# 09_ConsumptionBoard.net
KiCad netlist of a schematic drawn in Altium Designer
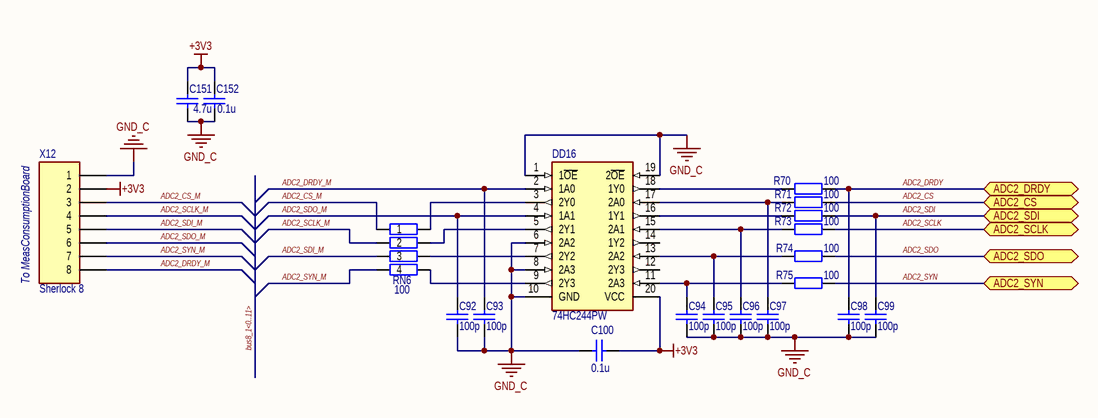
[diagram p0: 09_ConsumptionBoard.SchDoc]

(export (version "E")
  (design (tool "Eeschema 10.0.6"))
  (components
    (comp (ref "C92")
      (value "100p")
      (footprint "mainLib:SMD_C_0603")
      (description "SMD C 0603 MURATA 100V 5% NP0")
      (fields (field (name "PARTNUMBER") "GRM1885C2A101JA01") (field (name "MANUFACTURER") "MURATA"))
      (libsource (lib "mainRCLib") (part "C0603 100p 100V 5%"))
    )
    (comp (ref "C93")
      (value "100p")
      (footprint "mainLib:SMD_C_0603")
      (description "SMD C 0603 MURATA 100V 5% NP0")
      (fields (field (name "PARTNUMBER") "GRM1885C2A101JA01") (field (name "MANUFACTURER") "MURATA"))
      (libsource (lib "mainRCLib") (part "C0603 100p 100V 5%"))
    )
    (comp (ref "C94")
      (value "100p")
      (footprint "mainLib:SMD_C_0603")
      (description "SMD C 0603 MURATA 100V 5% NP0")
      (fields (field (name "PARTNUMBER") "GRM1885C2A101JA01") (field (name "MANUFACTURER") "MURATA"))
      (libsource (lib "mainRCLib") (part "C0603 100p 100V 5%"))
    )
    (comp (ref "C95")
      (value "100p")
      (footprint "mainLib:SMD_C_0603")
      (description "SMD C 0603 MURATA 100V 5% NP0")
      (fields (field (name "PARTNUMBER") "GRM1885C2A101JA01") (field (name "MANUFACTURER") "MURATA"))
      (libsource (lib "mainRCLib") (part "C0603 100p 100V 5%"))
    )
    (comp (ref "C96")
      (value "100p")
      (footprint "mainLib:SMD_C_0603")
      (description "SMD C 0603 MURATA 100V 5% NP0")
      (fields (field (name "PARTNUMBER") "GRM1885C2A101JA01") (field (name "MANUFACTURER") "MURATA"))
      (libsource (lib "mainRCLib") (part "C0603 100p 100V 5%"))
    )
    (comp (ref "C97")
      (value "100p")
      (footprint "mainLib:SMD_C_0603")
      (description "SMD C 0603 MURATA 100V 5% NP0")
      (fields (field (name "PARTNUMBER") "GRM1885C2A101JA01") (field (name "MANUFACTURER") "MURATA"))
      (libsource (lib "mainRCLib") (part "C0603 100p 100V 5%"))
    )
    (comp (ref "C98")
      (value "100p")
      (footprint "mainLib:SMD_C_0603")
      (description "SMD C 0603 MURATA 100V 5% NP0")
      (fields (field (name "PARTNUMBER") "GRM1885C2A101JA01") (field (name "MANUFACTURER") "MURATA"))
      (libsource (lib "mainRCLib") (part "C0603 100p 100V 5%"))
    )
    (comp (ref "C99")
      (value "100p")
      (footprint "mainLib:SMD_C_0603")
      (description "SMD C 0603 MURATA 100V 5% NP0")
      (fields (field (name "PARTNUMBER") "GRM1885C2A101JA01") (field (name "MANUFACTURER") "MURATA"))
      (libsource (lib "mainRCLib") (part "C0603 100p 100V 5%"))
    )
    (comp (ref "C100")
      (value "0.1u")
      (footprint "mainLib:SMD_C_0603")
      (description "SMD C 0603 MURATA 50V 10% X7R")
      (fields (field (name "PARTNUMBER") "GRM188R71H104K") (field (name "MANUFACTURER") "MURATA"))
      (libsource (lib "mainRCLib") (part "C0603 0.1u 50V 10%"))
    )
    (comp (ref "C151")
      (value "4.7u")
      (footprint "mainLib:SMD_C_0805")
      (description "SMD C 0805 MURATA 50V 5% NP0")
      (fields (field (name "PARTNUMBER") "GRM21BR61E475M") (field (name "MANUFACTURER") "MURATA"))
      (libsource (lib "mainRCLib") (part "C0805 4.7u 25V 20%  X5R"))
    )
    (comp (ref "C152")
      (value "0.1u")
      (footprint "mainLib:SMD_C_0603")
      (description "SMD C 0603 MURATA 50V 10% X7R")
      (fields (field (name "PARTNUMBER") "GRM188R71H104K") (field (name "MANUFACTURER") "MURATA"))
      (libsource (lib "mainRCLib") (part "C0603 0.1u 50V 10%"))
    )
    (comp (ref "DD16")
      (value "74HC244PW")
      (footprint "mainLib:TSSOP20")
      (description "Octal Buffer/Line Driver with 3-State Outputs, PW0020A")
      (fields (field (name "MANUFACTURER") "NXP"))
      (libsource (lib "mainLib") (part "74HC244PW"))
    )
    (comp (ref "R70")
      (value "100")
      (footprint "SMD_R_0603")
      (description "SMD R 0603 VISHAY 0.1W 75V 1% 100ppm")
      (fields (field (name "PARTNUMBER") "CRCW0603100RFK") (field (name "MANUFACTURER") "VISHAY"))
      (libsource (lib "mainRCLib") (part "R0603 100 1%"))
    )
    (comp (ref "R71")
      (value "100")
      (footprint "SMD_R_0603")
      (description "SMD R 0603 VISHAY 0.1W 75V 1% 100ppm")
      (fields (field (name "PARTNUMBER") "CRCW0603100RFK") (field (name "MANUFACTURER") "VISHAY"))
      (libsource (lib "mainRCLib") (part "R0603 100 1%"))
    )
    (comp (ref "R72")
      (value "100")
      (footprint "SMD_R_0603")
      (description "SMD R 0603 VISHAY 0.1W 75V 1% 100ppm")
      (fields (field (name "PARTNUMBER") "CRCW0603100RFK") (field (name "MANUFACTURER") "VISHAY"))
      (libsource (lib "mainRCLib") (part "R0603 100 1%"))
    )
    (comp (ref "R73")
      (value "100")
      (footprint "SMD_R_0603")
      (description "SMD R 0603 VISHAY 0.1W 75V 1% 100ppm")
      (fields (field (name "PARTNUMBER") "CRCW0603100RFK") (field (name "MANUFACTURER") "VISHAY"))
      (libsource (lib "mainRCLib") (part "R0603 100 1%"))
    )
    (comp (ref "R74")
      (value "100")
      (footprint "SMD_R_0603")
      (description "SMD R 0603 VISHAY 0.1W 75V 1% 100ppm")
      (fields (field (name "PARTNUMBER") "CRCW0603100RFK") (field (name "MANUFACTURER") "VISHAY"))
      (libsource (lib "mainRCLib") (part "R0603 100 1%"))
    )
    (comp (ref "R75")
      (value "100")
      (footprint "SMD_R_0603")
      (description "SMD R 0603 VISHAY 0.1W 75V 1% 100ppm")
      (fields (field (name "PARTNUMBER") "CRCW0603100RFK") (field (name "MANUFACTURER") "VISHAY"))
      (libsource (lib "mainRCLib") (part "R0603 100 1%"))
    )
    (comp (ref "RN6")
      (value "100")
      (footprint "mainLib:CRA06S")
      (description "SMD RESISTOR ARRAY VISHAY 0.063W 50V 1% 100ppm")
      (fields (field (name "PARTNUMBER") "CRA06S083100RF") (field (name "MANUFACTURER") "VISHAY"))
      (libsource (lib "mainRCLib") (part "CRA06S 4x100 1%"))
    )
    (comp (ref "X12")
      (value "Sherlock 8")
      (footprint "mainLib:35362-0850")
      (description "Sherlock 8 Side, 2A 125V 2mm")
      (fields (field (name "PARTNUMBER") "35362-0850") (field (name "MANUFACTURER") "MOLEX"))
      (libsource (lib "mainLib") (part "35362-0850"))
    )
  )
  (nets
    (net (code "2") (name "+3V3") (class "Default")
      (node (ref "C100") (pin "2") (pinfunction "2_2") (pintype "passive"))
      (node (ref "C151") (pin "2") (pinfunction "2_2") (pintype "passive"))
      (node (ref "C152") (pin "2") (pinfunction "2_2") (pintype "passive"))
      (node (ref "DD16") (pin "20") (pinfunction "VCC_20") (pintype "power_in"))
      (node (ref "X12") (pin "2") (pinfunction "2_2") (pintype "passive"))
    )
    (net (code "3") (name "/ADC2_CS") (class "Default")
      (node (ref "R71") (pin "2") (pinfunction "2_2") (pintype "passive"))
    )
    (net (code "4") (name "/ADC2_CS_M") (class "Default")
      (node (ref "RN6") (pin "1") (pinfunction "1_1") (pintype "passive"))
      (node (ref "X12") (pin "3") (pinfunction "3_3") (pintype "passive"))
    )
    (net (code "5") (name "/ADC2_DRDY") (class "Default")
      (node (ref "C98") (pin "1") (pinfunction "1_1") (pintype "passive"))
      (node (ref "R70") (pin "2") (pinfunction "2_2") (pintype "passive"))
    )
    (net (code "6") (name "/ADC2_DRDY_M") (class "Default")
      (node (ref "C93") (pin "1") (pinfunction "1_1") (pintype "passive"))
      (node (ref "DD16") (pin "2") (pinfunction "1A0_2") (pintype "input"))
      (node (ref "X12") (pin "8") (pinfunction "8_8") (pintype "passive"))
    )
    (net (code "7") (name "/ADC2_SCLK") (class "Default")
      (node (ref "R73") (pin "2") (pinfunction "2_2") (pintype "passive"))
    )
    (net (code "8") (name "/ADC2_SCLK_M") (class "Default")
      (node (ref "RN6") (pin "2") (pinfunction "2_2") (pintype "passive"))
      (node (ref "X12") (pin "4") (pinfunction "4_4") (pintype "passive"))
    )
    (net (code "9") (name "/ADC2_SDI") (class "Default")
      (node (ref "C99") (pin "1") (pinfunction "1_1") (pintype "passive"))
      (node (ref "R72") (pin "2") (pinfunction "2_2") (pintype "passive"))
    )
    (net (code "10") (name "/ADC2_SDI_M") (class "Default")
      (node (ref "RN6") (pin "3") (pinfunction "3_3") (pintype "passive"))
      (node (ref "X12") (pin "5") (pinfunction "5_5") (pintype "passive"))
    )
    (net (code "11") (name "/ADC2_SDO") (class "Default")
      (node (ref "R74") (pin "2") (pinfunction "2_2") (pintype "passive"))
    )
    (net (code "12") (name "/ADC2_SDO_M") (class "Default")
      (node (ref "C92") (pin "1") (pinfunction "1_1") (pintype "passive"))
      (node (ref "DD16") (pin "4") (pinfunction "1A1_4") (pintype "input"))
      (node (ref "X12") (pin "6") (pinfunction "6_6") (pintype "passive"))
    )
    (net (code "13") (name "/ADC2_SYN") (class "Default")
      (node (ref "R75") (pin "2") (pinfunction "2_2") (pintype "passive"))
    )
    (net (code "14") (name "/ADC2_SYN_M") (class "Default")
      (node (ref "RN6") (pin "4") (pinfunction "4_4") (pintype "passive"))
      (node (ref "X12") (pin "7") (pinfunction "7_7") (pintype "passive"))
    )
    (net (code "16") (name "GND_C") (class "Default")
      (node (ref "C100") (pin "1") (pinfunction "1_1") (pintype "passive"))
      (node (ref "C151") (pin "1") (pinfunction "1_1") (pintype "passive"))
      (node (ref "C152") (pin "1") (pinfunction "1_1") (pintype "passive"))
      (node (ref "C92") (pin "2") (pinfunction "2_2") (pintype "passive"))
      (node (ref "C93") (pin "2") (pinfunction "2_2") (pintype "passive"))
      (node (ref "C94") (pin "2") (pinfunction "2_2") (pintype "passive"))
      (node (ref "C95") (pin "2") (pinfunction "2_2") (pintype "passive"))
      (node (ref "C96") (pin "2") (pinfunction "2_2") (pintype "passive"))
      (node (ref "C97") (pin "2") (pinfunction "2_2") (pintype "passive"))
      (node (ref "C98") (pin "2") (pinfunction "2_2") (pintype "passive"))
      (node (ref "C99") (pin "2") (pinfunction "2_2") (pintype "passive"))
      (node (ref "DD16") (pin "1") (pinfunction "1~{OE}_1") (pintype "input"))
      (node (ref "DD16") (pin "10") (pinfunction "GND_10") (pintype "power_in"))
      (node (ref "DD16") (pin "19") (pinfunction "2~{OE}_19") (pintype "input"))
      (node (ref "DD16") (pin "6") (pinfunction "2A2_6") (pintype "input"))
      (node (ref "DD16") (pin "8") (pinfunction "2A3_8") (pintype "input"))
      (node (ref "X12") (pin "1") (pinfunction "1_1") (pintype "passive"))
    )
    (net (code "17") (name "Net-(C94-Pad1)") (class "Default")
      (node (ref "C94") (pin "1") (pinfunction "1_1") (pintype "passive"))
      (node (ref "DD16") (pin "11") (pinfunction "2A3_11") (pintype "input"))
      (node (ref "R75") (pin "1") (pinfunction "1_1") (pintype "passive"))
    )
    (net (code "18") (name "Net-(C95-Pad1)") (class "Default")
      (node (ref "C95") (pin "1") (pinfunction "1_1") (pintype "passive"))
      (node (ref "DD16") (pin "13") (pinfunction "2A2_13") (pintype "input"))
      (node (ref "R74") (pin "1") (pinfunction "1_1") (pintype "passive"))
    )
    (net (code "19") (name "Net-(DD16-1Y0)") (class "Default")
      (node (ref "DD16") (pin "18") (pinfunction "1Y0_18") (pintype "output"))
      (node (ref "R70") (pin "1") (pinfunction "1_1") (pintype "passive"))
    )
    (net (code "20") (name "Net-(DD16-1Y1)") (class "Default")
      (node (ref "DD16") (pin "16") (pinfunction "1Y1_16") (pintype "output"))
      (node (ref "R72") (pin "1") (pinfunction "1_1") (pintype "passive"))
    )
    (net (code "21") (name "Net-(DD16-2A0)") (class "Default")
      (node (ref "C97") (pin "1") (pinfunction "1_1") (pintype "passive"))
      (node (ref "DD16") (pin "17") (pinfunction "2A0_17") (pintype "input"))
      (node (ref "R71") (pin "1") (pinfunction "1_1") (pintype "passive"))
    )
    (net (code "22") (name "Net-(DD16-2A1)") (class "Default")
      (node (ref "C96") (pin "1") (pinfunction "1_1") (pintype "passive"))
      (node (ref "DD16") (pin "15") (pinfunction "2A1_15") (pintype "input"))
      (node (ref "R73") (pin "1") (pinfunction "1_1") (pintype "passive"))
    )
    (net (code "23") (name "Net-(DD16-2Y0)") (class "Default")
      (node (ref "DD16") (pin "3") (pinfunction "2Y0_3") (pintype "output"))
      (node (ref "RN6") (pin "8") (pinfunction "8_8") (pintype "passive"))
    )
    (net (code "24") (name "Net-(DD16-2Y1)") (class "Default")
      (node (ref "DD16") (pin "5") (pinfunction "2Y1_5") (pintype "output"))
      (node (ref "RN6") (pin "7") (pinfunction "7_7") (pintype "passive"))
    )
    (net (code "25") (name "Net-(DD16-2Y2)") (class "Default")
      (node (ref "DD16") (pin "7") (pinfunction "2Y2_7") (pintype "output"))
      (node (ref "RN6") (pin "6") (pinfunction "6_6") (pintype "passive"))
    )
    (net (code "26") (name "Net-(DD16-2Y3-Pad9)") (class "Default")
      (node (ref "DD16") (pin "9") (pinfunction "2Y3_9") (pintype "output"))
      (node (ref "RN6") (pin "5") (pinfunction "5_5") (pintype "passive"))
    )
    (net (code "27") (name "unconnected-(DD16-1Y2-Pad14)") (class "Default")
      (node (ref "DD16") (pin "14") (pinfunction "1Y2_14") (pintype "output"))
    )
    (net (code "28") (name "unconnected-(DD16-2Y3-Pad12)") (class "Default")
      (node (ref "DD16") (pin "12") (pinfunction "2Y3_12") (pintype "output"))
    )
  )
)
